# Model-Train-Controller.net
KiCad netlist of a schematic drawn in EAGLE
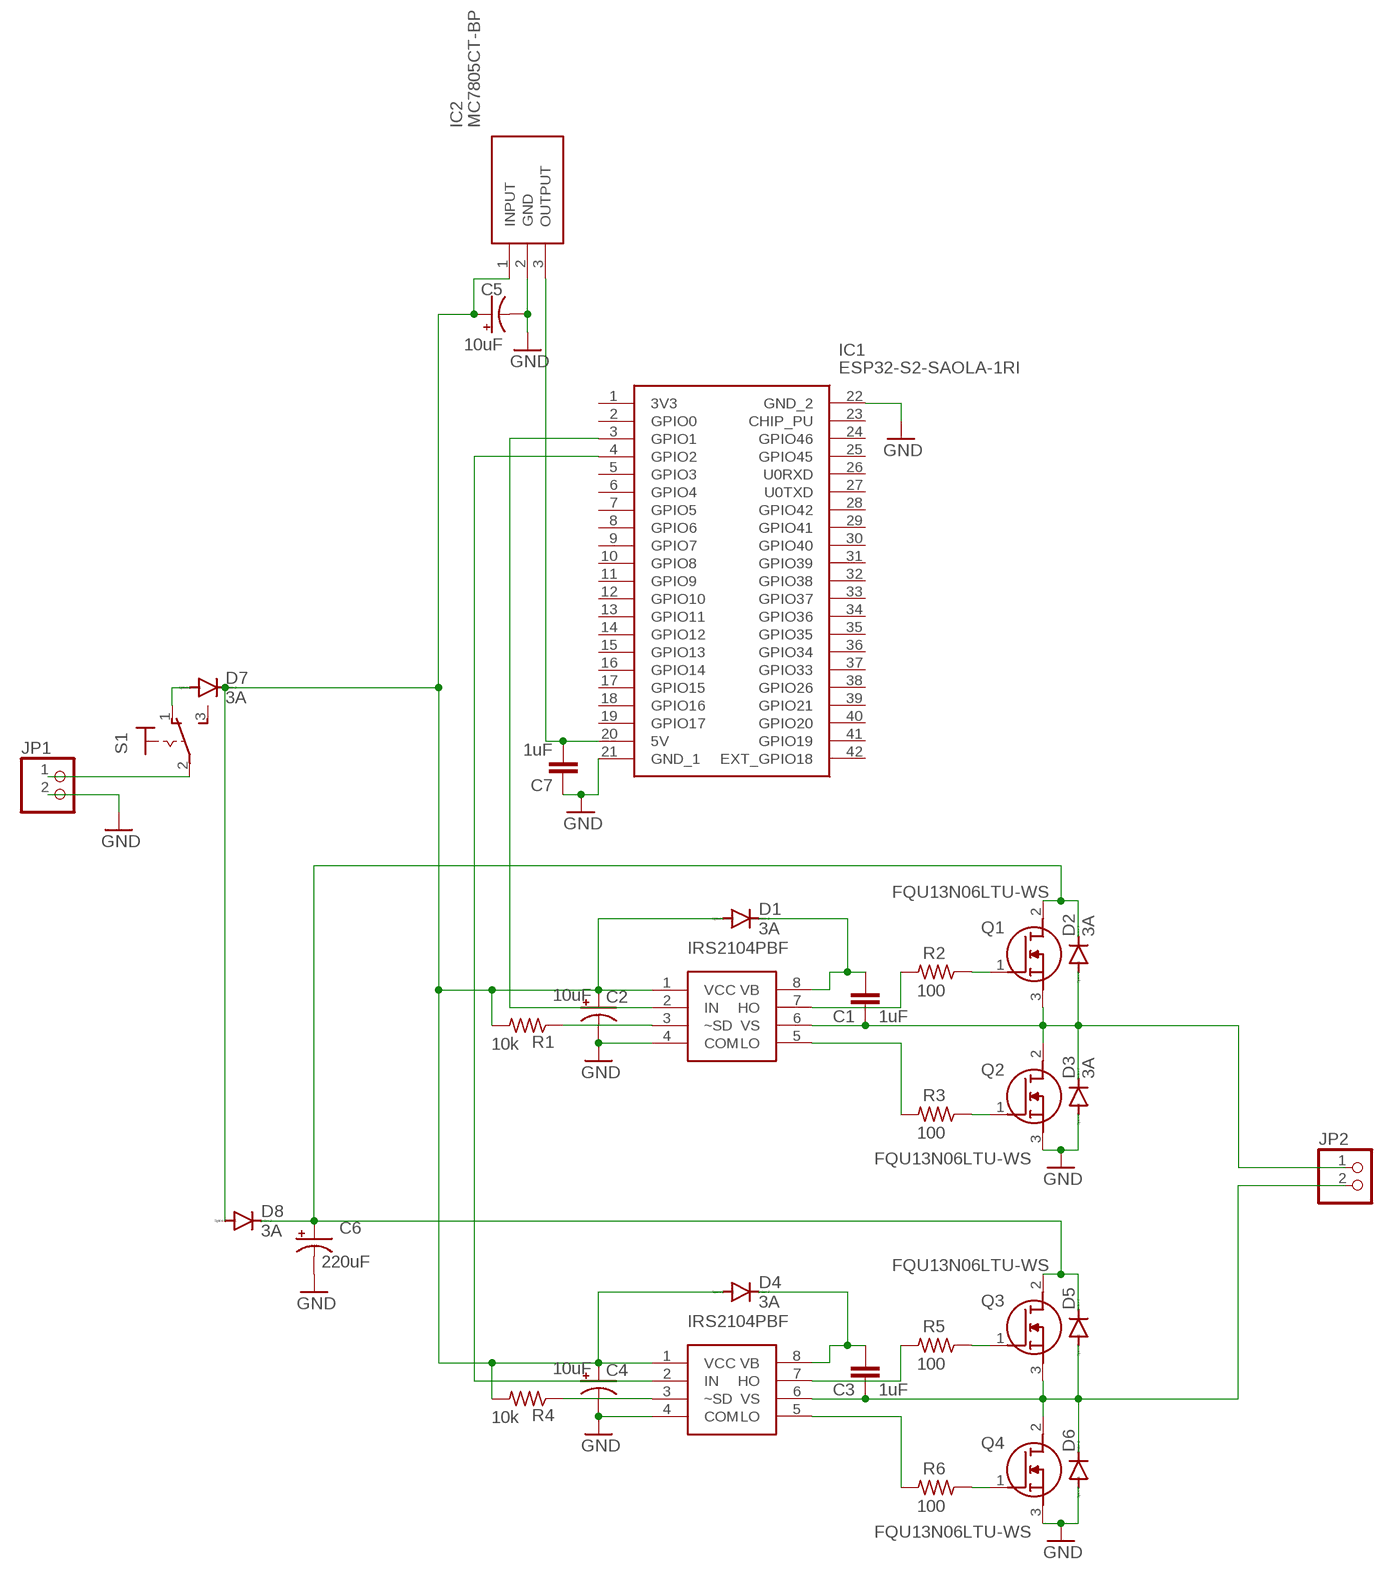
[diagram p0: schematic, sheet 1]

(export (version "E")
  (design (tool "Eeschema 10.0.6"))
  (components
    (comp (ref "C1")
      (value "1uF")
      (footprint "eagle-import:C025-030X050")
      (libsource (lib "eagle-import") (part "C-EU025-030X050"))
    )
    (comp (ref "C2")
      (value "10uF")
      (footprint "eagle-import:E2-5")
      (libsource (lib "eagle-import") (part "CPOL-USE2-5"))
    )
    (comp (ref "C3")
      (value "1uF")
      (footprint "eagle-import:C025-030X050")
      (libsource (lib "eagle-import") (part "C-EU025-030X050"))
    )
    (comp (ref "C4")
      (value "10uF")
      (footprint "eagle-import:E2-5")
      (libsource (lib "eagle-import") (part "CPOL-USE2-5"))
    )
    (comp (ref "C5")
      (value "10uF")
      (footprint "eagle-import:E2-5")
      (libsource (lib "eagle-import") (part "CPOL-USE2-5"))
    )
    (comp (ref "C6")
      (value "220uF")
      (footprint "eagle-import:E2-5")
      (libsource (lib "eagle-import") (part "CPOL-USE2-5"))
    )
    (comp (ref "C7")
      (value "1uF")
      (footprint "eagle-import:C025-030X050")
      (libsource (lib "eagle-import") (part "C-EU025-030X050"))
    )
    (comp (ref "D1")
      (value "3A")
      (footprint "eagle-import:DO201-15")
      (libsource (lib "eagle-import") (part "DIODE-DO201-15"))
    )
    (comp (ref "D2")
      (value "3A")
      (footprint "eagle-import:DO201-15")
      (libsource (lib "eagle-import") (part "DIODE-DO201-15"))
    )
    (comp (ref "D3")
      (value "3A")
      (footprint "eagle-import:DO201-15")
      (libsource (lib "eagle-import") (part "DIODE-DO201-15"))
    )
    (comp (ref "D4")
      (value "3A")
      (footprint "eagle-import:DO201-15")
      (libsource (lib "eagle-import") (part "DIODE-DO201-15"))
    )
    (comp (ref "D5")
      (value "DIODE-DO201-15")
      (footprint "eagle-import:DO201-15")
      (libsource (lib "eagle-import") (part "DIODE-DO201-15"))
    )
    (comp (ref "D6")
      (value "DIODE-DO201-15")
      (footprint "eagle-import:DO201-15")
      (libsource (lib "eagle-import") (part "DIODE-DO201-15"))
    )
    (comp (ref "D7")
      (value "3A")
      (footprint "eagle-import:DO201-15")
      (libsource (lib "eagle-import") (part "DIODE-DO201-15"))
    )
    (comp (ref "D8")
      (value "3A")
      (footprint "eagle-import:DO201-15")
      (libsource (lib "eagle-import") (part "DIODE-DO201-15"))
    )
    (comp (ref "IC1")
      (value "ESP32-S2-SAOLA-1RI")
      (footprint "eagle-import:ESP32S2SAOLA1RI")
      (fields
        (field (name "MANUFACTURER_PART_NUMBER") "ESP32-S2-Saola-1RI")
        (field (name "MOUSER_PART_NUMBER") "356-ESP32-S2SAOLA1RI")
      )
      (libsource (lib "eagle-import") (part "ESP32-S2-SAOLA-1RI"))
    )
    (comp (ref "IC2")
      (value "MC7805CT-BP")
      (footprint "eagle-import:TO254P482X1016X2325-3P")
      (fields (field (name "MOUSER_PART_NUMBER") "833-MC7805CT-BP"))
      (libsource (lib "eagle-import") (part "MC7805CT-BP"))
    )
    (comp (ref "JP1")
      (value "PINHD-1X2")
      (footprint "eagle-import:1X02")
      (libsource (lib "eagle-import") (part "PINHD-1X2"))
    )
    (comp (ref "JP2")
      (value "PINHD-1X2")
      (footprint "eagle-import:1X02")
      (libsource (lib "eagle-import") (part "PINHD-1X2"))
    )
    (comp (ref "Q1")
      (value "FQU13N06LTU-WS")
      (footprint "eagle-import:TO229P250X658X985-3P")
      (fields (field (name "MOUSER_PART_NUMBER") "512-FQU13N06LTU_WS"))
      (libsource (lib "eagle-import") (part "FQU13N06LTU-WS"))
    )
    (comp (ref "Q2")
      (value "FQU13N06LTU-WS")
      (footprint "eagle-import:TO229P250X658X985-3P")
      (fields (field (name "MOUSER_PART_NUMBER") "512-FQU13N06LTU_WS"))
      (libsource (lib "eagle-import") (part "FQU13N06LTU-WS"))
    )
    (comp (ref "Q3")
      (value "FQU13N06LTU-WS")
      (footprint "eagle-import:TO229P250X658X985-3P")
      (fields (field (name "MOUSER_PART_NUMBER") "512-FQU13N06LTU_WS"))
      (libsource (lib "eagle-import") (part "FQU13N06LTU-WS"))
    )
    (comp (ref "Q4")
      (value "FQU13N06LTU-WS")
      (footprint "eagle-import:TO229P250X658X985-3P")
      (fields (field (name "MOUSER_PART_NUMBER") "512-FQU13N06LTU_WS"))
      (libsource (lib "eagle-import") (part "FQU13N06LTU-WS"))
    )
    (comp (ref "R1")
      (value "10k")
      (footprint "eagle-import:0204_5")
      (libsource (lib "eagle-import") (part "R-US_0204/5"))
    )
    (comp (ref "R2")
      (value "100")
      (footprint "eagle-import:0204_5")
      (libsource (lib "eagle-import") (part "R-US_0204/5"))
    )
    (comp (ref "R3")
      (value "100")
      (footprint "eagle-import:0204_5")
      (libsource (lib "eagle-import") (part "R-US_0204/5"))
    )
    (comp (ref "R4")
      (value "10k")
      (footprint "eagle-import:0204_5")
      (libsource (lib "eagle-import") (part "R-US_0204/5"))
    )
    (comp (ref "R5")
      (value "100")
      (footprint "eagle-import:0204_5")
      (libsource (lib "eagle-import") (part "R-US_0204/5"))
    )
    (comp (ref "R6")
      (value "100")
      (footprint "eagle-import:0204_5")
      (libsource (lib "eagle-import") (part "R-US_0204/5"))
    )
    (comp (ref "S1")
      (value "320-916")
      (footprint "eagle-import:320-916")
      (libsource (lib "eagle-import") (part "320-916"))
    )
    (comp (ref "U$1")
      (value "IRS2104PBF")
      (footprint "eagle-import:DIL08")
      (libsource (lib "eagle-import") (part "IRS2104PBF"))
    )
    (comp (ref "U$2")
      (value "IRS2104PBF")
      (footprint "eagle-import:DIL08")
      (libsource (lib "eagle-import") (part "IRS2104PBF"))
    )
  )
  (nets
    (net (code "1") (name "GND") (class "Default")
      (node (ref "C2") (pin "-") (pinfunction "-_-") (pintype "passive"))
      (node (ref "C4") (pin "-") (pinfunction "-_-") (pintype "passive"))
      (node (ref "C5") (pin "-") (pinfunction "-_-") (pintype "passive"))
      (node (ref "C6") (pin "-") (pinfunction "-_-") (pintype "passive"))
      (node (ref "C7") (pin "1") (pinfunction "1_1") (pintype "passive"))
      (node (ref "D3") (pin "A") (pinfunction "A_A") (pintype "passive"))
      (node (ref "D6") (pin "A") (pinfunction "A_A") (pintype "passive"))
      (node (ref "IC1") (pin "21") (pinfunction "GND_1_21") (pintype "bidirectional"))
      (node (ref "IC1") (pin "22") (pinfunction "GND_2_22") (pintype "bidirectional"))
      (node (ref "IC2") (pin "2") (pinfunction "GND_2") (pintype "bidirectional"))
      (node (ref "JP1") (pin "2") (pinfunction "2_2") (pintype "passive"))
      (node (ref "Q2") (pin "3") (pinfunction "S_3") (pintype "bidirectional"))
      (node (ref "Q4") (pin "3") (pinfunction "S_3") (pintype "bidirectional"))
      (node (ref "U$1") (pin "4") (pinfunction "COM_4") (pintype "power_in"))
      (node (ref "U$2") (pin "4") (pinfunction "COM_4") (pintype "power_in"))
    )
    (net (code "2") (name "Net-(IC1-5V)") (class "Default")
      (node (ref "C7") (pin "2") (pinfunction "2_2") (pintype "passive"))
      (node (ref "IC1") (pin "20") (pinfunction "5V_20") (pintype "bidirectional"))
      (node (ref "IC2") (pin "3") (pinfunction "OUTPUT_3") (pintype "bidirectional"))
    )
    (net (code "3") (name "Net-(IC1-GPIO1)") (class "Default")
      (node (ref "IC1") (pin "3") (pinfunction "GPIO1_3") (pintype "bidirectional"))
      (node (ref "U$1") (pin "2") (pinfunction "IN_2") (pintype "input"))
    )
    (net (code "4") (name "Net-(IC1-GPIO2)") (class "Default")
      (node (ref "IC1") (pin "4") (pinfunction "GPIO2_4") (pintype "bidirectional"))
      (node (ref "U$2") (pin "2") (pinfunction "IN_2") (pintype "input"))
    )
    (net (code "5") (name "Net-(IC2-INPUT)") (class "Default")
      (node (ref "C2") (pin "+") (pinfunction "+_+") (pintype "passive"))
      (node (ref "C4") (pin "+") (pinfunction "+_+") (pintype "passive"))
      (node (ref "C5") (pin "+") (pinfunction "+_+") (pintype "passive"))
      (node (ref "D1") (pin "A") (pinfunction "A_A") (pintype "passive"))
      (node (ref "D4") (pin "A") (pinfunction "A_A") (pintype "passive"))
      (node (ref "D7") (pin "C") (pinfunction "C_C") (pintype "passive"))
      (node (ref "D8") (pin "A") (pinfunction "A_A") (pintype "passive"))
      (node (ref "IC2") (pin "1") (pinfunction "INPUT_1") (pintype "bidirectional"))
      (node (ref "R1") (pin "2") (pinfunction "2_2") (pintype "passive"))
      (node (ref "R4") (pin "2") (pinfunction "2_2") (pintype "passive"))
      (node (ref "U$1") (pin "1") (pinfunction "VCC_1") (pintype "power_in"))
      (node (ref "U$2") (pin "1") (pinfunction "VCC_1") (pintype "power_in"))
    )
    (net (code "6") (name "Net-(Q1-D)") (class "Default")
      (node (ref "C6") (pin "+") (pinfunction "+_+") (pintype "passive"))
      (node (ref "D2") (pin "C") (pinfunction "C_C") (pintype "passive"))
      (node (ref "D5") (pin "C") (pinfunction "C_C") (pintype "passive"))
      (node (ref "D8") (pin "C") (pinfunction "C_C") (pintype "passive"))
      (node (ref "Q1") (pin "2") (pinfunction "D_2") (pintype "bidirectional"))
      (node (ref "Q3") (pin "2") (pinfunction "D_2") (pintype "bidirectional"))
    )
    (net (code "7") (name "Net-(Q1-G)") (class "Default")
      (node (ref "Q1") (pin "1") (pinfunction "G_1") (pintype "bidirectional"))
      (node (ref "R2") (pin "1") (pinfunction "1_1") (pintype "passive"))
    )
    (net (code "8") (name "Net-(Q1-S)") (class "Default")
      (node (ref "C1") (pin "1") (pinfunction "1_1") (pintype "passive"))
      (node (ref "D2") (pin "A") (pinfunction "A_A") (pintype "passive"))
      (node (ref "D3") (pin "C") (pinfunction "C_C") (pintype "passive"))
      (node (ref "JP2") (pin "1") (pinfunction "1_1") (pintype "passive"))
      (node (ref "Q1") (pin "3") (pinfunction "S_3") (pintype "bidirectional"))
      (node (ref "Q2") (pin "2") (pinfunction "D_2") (pintype "bidirectional"))
      (node (ref "U$1") (pin "6") (pinfunction "VS_6") (pintype "input"))
    )
    (net (code "9") (name "Net-(Q2-G)") (class "Default")
      (node (ref "Q2") (pin "1") (pinfunction "G_1") (pintype "bidirectional"))
      (node (ref "R3") (pin "1") (pinfunction "1_1") (pintype "passive"))
    )
    (net (code "10") (name "Net-(Q3-G)") (class "Default")
      (node (ref "Q3") (pin "1") (pinfunction "G_1") (pintype "bidirectional"))
      (node (ref "R5") (pin "1") (pinfunction "1_1") (pintype "passive"))
    )
    (net (code "11") (name "Net-(Q3-S)") (class "Default")
      (node (ref "C3") (pin "1") (pinfunction "1_1") (pintype "passive"))
      (node (ref "D5") (pin "A") (pinfunction "A_A") (pintype "passive"))
      (node (ref "D6") (pin "C") (pinfunction "C_C") (pintype "passive"))
      (node (ref "JP2") (pin "2") (pinfunction "2_2") (pintype "passive"))
      (node (ref "Q3") (pin "3") (pinfunction "S_3") (pintype "bidirectional"))
      (node (ref "Q4") (pin "2") (pinfunction "D_2") (pintype "bidirectional"))
      (node (ref "U$2") (pin "6") (pinfunction "VS_6") (pintype "input"))
    )
    (net (code "12") (name "Net-(Q4-G)") (class "Default")
      (node (ref "Q4") (pin "1") (pinfunction "G_1") (pintype "bidirectional"))
      (node (ref "R6") (pin "1") (pinfunction "1_1") (pintype "passive"))
    )
    (net (code "13") (name "Net-(S1-O)") (class "Default")
      (node (ref "D7") (pin "A") (pinfunction "A_A") (pintype "passive"))
      (node (ref "S1") (pin "1") (pinfunction "O_1") (pintype "passive"))
    )
    (net (code "14") (name "Net-(S1-P)") (class "Default")
      (node (ref "JP1") (pin "1") (pinfunction "1_1") (pintype "passive"))
      (node (ref "S1") (pin "2") (pinfunction "P_2") (pintype "passive"))
    )
    (net (code "15") (name "Net-(U$1-HO)") (class "Default")
      (node (ref "R2") (pin "2") (pinfunction "2_2") (pintype "passive"))
      (node (ref "U$1") (pin "7") (pinfunction "HO_7") (pintype "output"))
    )
    (net (code "16") (name "Net-(U$1-LO)") (class "Default")
      (node (ref "R3") (pin "2") (pinfunction "2_2") (pintype "passive"))
      (node (ref "U$1") (pin "5") (pinfunction "LO_5") (pintype "output"))
    )
    (net (code "17") (name "Net-(U$1-VB)") (class "Default")
      (node (ref "C1") (pin "2") (pinfunction "2_2") (pintype "passive"))
      (node (ref "D1") (pin "C") (pinfunction "C_C") (pintype "passive"))
      (node (ref "U$1") (pin "8") (pinfunction "VB_8") (pintype "open_collector"))
    )
    (net (code "18") (name "Net-(U$1-~{SD})") (class "Default")
      (node (ref "R1") (pin "1") (pinfunction "1_1") (pintype "passive"))
      (node (ref "U$1") (pin "3") (pinfunction "~{SD}_3") (pintype "input"))
    )
    (net (code "19") (name "Net-(U$2-HO)") (class "Default")
      (node (ref "R5") (pin "2") (pinfunction "2_2") (pintype "passive"))
      (node (ref "U$2") (pin "7") (pinfunction "HO_7") (pintype "output"))
    )
    (net (code "20") (name "Net-(U$2-LO)") (class "Default")
      (node (ref "R6") (pin "2") (pinfunction "2_2") (pintype "passive"))
      (node (ref "U$2") (pin "5") (pinfunction "LO_5") (pintype "output"))
    )
    (net (code "21") (name "Net-(U$2-VB)") (class "Default")
      (node (ref "C3") (pin "2") (pinfunction "2_2") (pintype "passive"))
      (node (ref "D4") (pin "C") (pinfunction "C_C") (pintype "passive"))
      (node (ref "U$2") (pin "8") (pinfunction "VB_8") (pintype "open_collector"))
    )
    (net (code "22") (name "Net-(U$2-~{SD})") (class "Default")
      (node (ref "R4") (pin "1") (pinfunction "1_1") (pintype "passive"))
      (node (ref "U$2") (pin "3") (pinfunction "~{SD}_3") (pintype "input"))
    )
    (net (code "23") (name "unconnected-(IC1-3V3-Pad1)") (class "Default")
      (node (ref "IC1") (pin "1") (pinfunction "3V3_1") (pintype "bidirectional"))
    )
    (net (code "24") (name "unconnected-(IC1-CHIP_PU-Pad23)") (class "Default")
      (node (ref "IC1") (pin "23") (pinfunction "CHIP_PU_23") (pintype "bidirectional"))
    )
    (net (code "25") (name "unconnected-(IC1-EXT_GPIO18-Pad42)") (class "Default")
      (node (ref "IC1") (pin "42") (pinfunction "EXT_GPIO18_42") (pintype "bidirectional"))
    )
    (net (code "26") (name "unconnected-(IC1-GPIO0-Pad2)") (class "Default")
      (node (ref "IC1") (pin "2") (pinfunction "GPIO0_2") (pintype "bidirectional"))
    )
    (net (code "27") (name "unconnected-(IC1-GPIO3-Pad5)") (class "Default")
      (node (ref "IC1") (pin "5") (pinfunction "GPIO3_5") (pintype "bidirectional"))
    )
    (net (code "28") (name "unconnected-(IC1-GPIO4-Pad6)") (class "Default")
      (node (ref "IC1") (pin "6") (pinfunction "GPIO4_6") (pintype "bidirectional"))
    )
    (net (code "29") (name "unconnected-(IC1-GPIO5-Pad7)") (class "Default")
      (node (ref "IC1") (pin "7") (pinfunction "GPIO5_7") (pintype "bidirectional"))
    )
    (net (code "30") (name "unconnected-(IC1-GPIO6-Pad8)") (class "Default")
      (node (ref "IC1") (pin "8") (pinfunction "GPIO6_8") (pintype "bidirectional"))
    )
    (net (code "31") (name "unconnected-(IC1-GPIO7-Pad9)") (class "Default")
      (node (ref "IC1") (pin "9") (pinfunction "GPIO7_9") (pintype "bidirectional"))
    )
    (net (code "32") (name "unconnected-(IC1-GPIO8-Pad10)") (class "Default")
      (node (ref "IC1") (pin "10") (pinfunction "GPIO8_10") (pintype "bidirectional"))
    )
    (net (code "33") (name "unconnected-(IC1-GPIO9-Pad11)") (class "Default")
      (node (ref "IC1") (pin "11") (pinfunction "GPIO9_11") (pintype "bidirectional"))
    )
    (net (code "34") (name "unconnected-(IC1-GPIO10-Pad12)") (class "Default")
      (node (ref "IC1") (pin "12") (pinfunction "GPIO10_12") (pintype "bidirectional"))
    )
    (net (code "35") (name "unconnected-(IC1-GPIO11-Pad13)") (class "Default")
      (node (ref "IC1") (pin "13") (pinfunction "GPIO11_13") (pintype "bidirectional"))
    )
    (net (code "36") (name "unconnected-(IC1-GPIO12-Pad14)") (class "Default")
      (node (ref "IC1") (pin "14") (pinfunction "GPIO12_14") (pintype "bidirectional"))
    )
    (net (code "37") (name "unconnected-(IC1-GPIO13-Pad15)") (class "Default")
      (node (ref "IC1") (pin "15") (pinfunction "GPIO13_15") (pintype "bidirectional"))
    )
    (net (code "38") (name "unconnected-(IC1-GPIO14-Pad16)") (class "Default")
      (node (ref "IC1") (pin "16") (pinfunction "GPIO14_16") (pintype "bidirectional"))
    )
    (net (code "39") (name "unconnected-(IC1-GPIO15-Pad17)") (class "Default")
      (node (ref "IC1") (pin "17") (pinfunction "GPIO15_17") (pintype "bidirectional"))
    )
    (net (code "40") (name "unconnected-(IC1-GPIO16-Pad18)") (class "Default")
      (node (ref "IC1") (pin "18") (pinfunction "GPIO16_18") (pintype "bidirectional"))
    )
    (net (code "41") (name "unconnected-(IC1-GPIO17-Pad19)") (class "Default")
      (node (ref "IC1") (pin "19") (pinfunction "GPIO17_19") (pintype "bidirectional"))
    )
    (net (code "42") (name "unconnected-(IC1-GPIO19-Pad41)") (class "Default")
      (node (ref "IC1") (pin "41") (pinfunction "GPIO19_41") (pintype "bidirectional"))
    )
    (net (code "43") (name "unconnected-(IC1-GPIO20-Pad40)") (class "Default")
      (node (ref "IC1") (pin "40") (pinfunction "GPIO20_40") (pintype "bidirectional"))
    )
    (net (code "44") (name "unconnected-(IC1-GPIO21-Pad39)") (class "Default")
      (node (ref "IC1") (pin "39") (pinfunction "GPIO21_39") (pintype "bidirectional"))
    )
    (net (code "45") (name "unconnected-(IC1-GPIO26-Pad38)") (class "Default")
      (node (ref "IC1") (pin "38") (pinfunction "GPIO26_38") (pintype "bidirectional"))
    )
    (net (code "46") (name "unconnected-(IC1-GPIO33-Pad37)") (class "Default")
      (node (ref "IC1") (pin "37") (pinfunction "GPIO33_37") (pintype "bidirectional"))
    )
    (net (code "47") (name "unconnected-(IC1-GPIO34-Pad36)") (class "Default")
      (node (ref "IC1") (pin "36") (pinfunction "GPIO34_36") (pintype "bidirectional"))
    )
    (net (code "48") (name "unconnected-(IC1-GPIO35-Pad35)") (class "Default")
      (node (ref "IC1") (pin "35") (pinfunction "GPIO35_35") (pintype "bidirectional"))
    )
    (net (code "49") (name "unconnected-(IC1-GPIO36-Pad34)") (class "Default")
      (node (ref "IC1") (pin "34") (pinfunction "GPIO36_34") (pintype "bidirectional"))
    )
    (net (code "50") (name "unconnected-(IC1-GPIO37-Pad33)") (class "Default")
      (node (ref "IC1") (pin "33") (pinfunction "GPIO37_33") (pintype "bidirectional"))
    )
    (net (code "51") (name "unconnected-(IC1-GPIO38-Pad32)") (class "Default")
      (node (ref "IC1") (pin "32") (pinfunction "GPIO38_32") (pintype "bidirectional"))
    )
    (net (code "52") (name "unconnected-(IC1-GPIO39-Pad31)") (class "Default")
      (node (ref "IC1") (pin "31") (pinfunction "GPIO39_31") (pintype "bidirectional"))
    )
    (net (code "53") (name "unconnected-(IC1-GPIO40-Pad30)") (class "Default")
      (node (ref "IC1") (pin "30") (pinfunction "GPIO40_30") (pintype "bidirectional"))
    )
    (net (code "54") (name "unconnected-(IC1-GPIO41-Pad29)") (class "Default")
      (node (ref "IC1") (pin "29") (pinfunction "GPIO41_29") (pintype "bidirectional"))
    )
    (net (code "55") (name "unconnected-(IC1-GPIO42-Pad28)") (class "Default")
      (node (ref "IC1") (pin "28") (pinfunction "GPIO42_28") (pintype "bidirectional"))
    )
    (net (code "56") (name "unconnected-(IC1-GPIO45-Pad25)") (class "Default")
      (node (ref "IC1") (pin "25") (pinfunction "GPIO45_25") (pintype "bidirectional"))
    )
    (net (code "57") (name "unconnected-(IC1-GPIO46-Pad24)") (class "Default")
      (node (ref "IC1") (pin "24") (pinfunction "GPIO46_24") (pintype "bidirectional"))
    )
    (net (code "58") (name "unconnected-(IC1-U0RXD-Pad26)") (class "Default")
      (node (ref "IC1") (pin "26") (pinfunction "U0RXD_26") (pintype "bidirectional"))
    )
    (net (code "59") (name "unconnected-(IC1-U0TXD-Pad27)") (class "Default")
      (node (ref "IC1") (pin "27") (pinfunction "U0TXD_27") (pintype "bidirectional"))
    )
    (net (code "60") (name "unconnected-(S1-S-Pad3)") (class "Default")
      (node (ref "S1") (pin "3") (pinfunction "S_3") (pintype "passive"))
    )
  )
)
